# VGA.net
KiCad netlist of a schematic drawn in Altium Designer
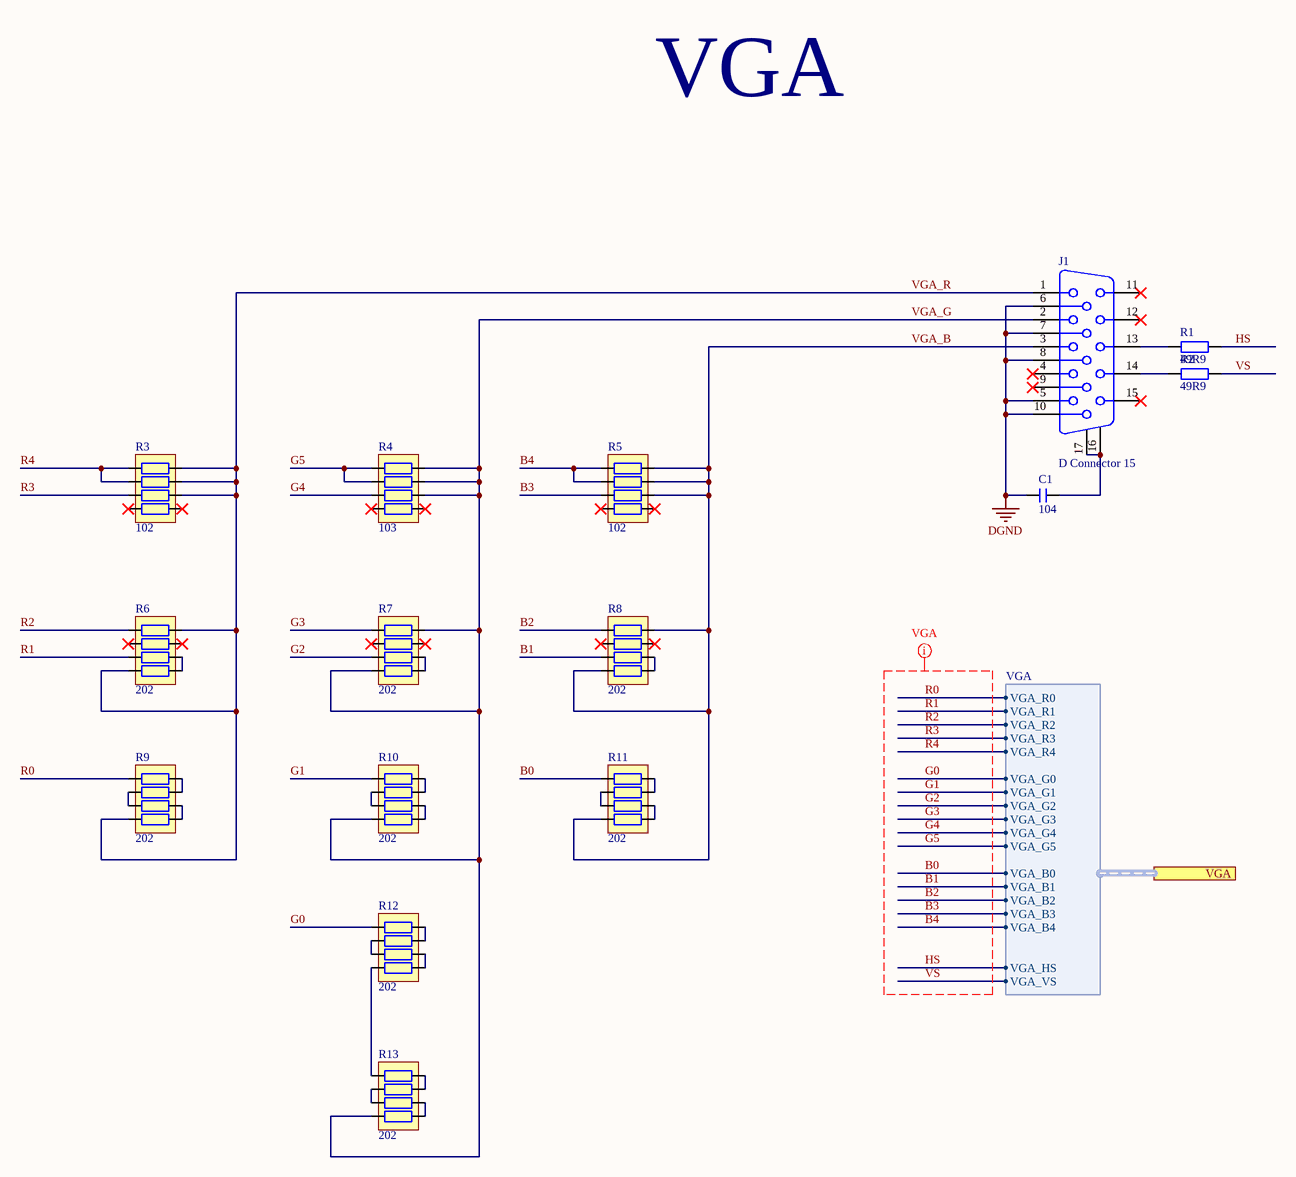
[diagram p0: VGA.SchDoc]

(export (version "E")
  (design (tool "Eeschema 10.0.6"))
  (components
    (comp (ref "C1")
      (value "104")
      (footprint "C 0402_M")
      (description "无极性贴片电容")
      (fields (field (name "版权归属") "源创客"))
      (libsource (lib "3.1   - 电阻-电容-电感") (part "C"))
    )
    (comp (ref "J1")
      (value "D Connector 15")
      (footprint "VGA15b")
      (description "VGA通讯端口")
      (fields (field (name "版权归属") "源创客"))
      (libsource (lib "4.1   - 接口类") (part "D Connector 15"))
    )
    (comp (ref "R1")
      (value "49R9")
      (footprint "R 0402_M")
      (description "贴片电阻")
      (fields (field (name "版权归属") "源创客"))
      (libsource (lib "3.1   - 电阻-电容-电感") (part "R"))
    )
    (comp (ref "R2")
      (value "49R9")
      (footprint "R 0402_M")
      (description "贴片电阻")
      (fields (field (name "版权归属") "源创客"))
      (libsource (lib "3.1   - 电阻-电容-电感") (part "R"))
    )
    (comp (ref "R3")
      (value "102")
      (footprint "RCA-8P4R-0402")
      (description "贴片网络排阻")
      (fields (field (name "版权归属") "源创客"))
      (libsource (lib "3.1   - 电阻-电容-电感") (part "R-8P4R"))
    )
    (comp (ref "R4")
      (value "103")
      (footprint "RCA-8P4R-0402")
      (description "贴片网络排阻")
      (fields (field (name "版权归属") "源创客"))
      (libsource (lib "3.1   - 电阻-电容-电感") (part "R-8P4R"))
    )
    (comp (ref "R5")
      (value "102")
      (footprint "RCA-8P4R-0402")
      (description "贴片网络排阻")
      (fields (field (name "版权归属") "源创客"))
      (libsource (lib "3.1   - 电阻-电容-电感") (part "R-8P4R"))
    )
    (comp (ref "R6")
      (value "202")
      (footprint "RCA-8P4R-0402")
      (description "贴片网络排阻")
      (fields (field (name "版权归属") "源创客"))
      (libsource (lib "3.1   - 电阻-电容-电感") (part "R-8P4R"))
    )
    (comp (ref "R7")
      (value "202")
      (footprint "RCA-8P4R-0402")
      (description "贴片网络排阻")
      (fields (field (name "版权归属") "源创客"))
      (libsource (lib "3.1   - 电阻-电容-电感") (part "R-8P4R"))
    )
    (comp (ref "R8")
      (value "202")
      (footprint "RCA-8P4R-0402")
      (description "贴片网络排阻")
      (fields (field (name "版权归属") "源创客"))
      (libsource (lib "3.1   - 电阻-电容-电感") (part "R-8P4R"))
    )
    (comp (ref "R9")
      (value "202")
      (footprint "RCA-8P4R-0402")
      (description "贴片网络排阻")
      (fields (field (name "版权归属") "源创客"))
      (libsource (lib "3.1   - 电阻-电容-电感") (part "R-8P4R"))
    )
    (comp (ref "R10")
      (value "202")
      (footprint "RCA-8P4R-0402")
      (description "贴片网络排阻")
      (fields (field (name "版权归属") "源创客"))
      (libsource (lib "3.1   - 电阻-电容-电感") (part "R-8P4R"))
    )
    (comp (ref "R11")
      (value "202")
      (footprint "RCA-8P4R-0402")
      (description "贴片网络排阻")
      (fields (field (name "版权归属") "源创客"))
      (libsource (lib "3.1   - 电阻-电容-电感") (part "R-8P4R"))
    )
    (comp (ref "R12")
      (value "202")
      (footprint "RCA-8P4R-0402")
      (description "贴片网络排阻")
      (fields (field (name "版权归属") "源创客"))
      (libsource (lib "3.1   - 电阻-电容-电感") (part "R-8P4R"))
    )
    (comp (ref "R13")
      (value "202")
      (footprint "RCA-8P4R-0402")
      (description "贴片网络排阻")
      (fields (field (name "版权归属") "源创客"))
      (libsource (lib "3.1   - 电阻-电容-电感") (part "R-8P4R"))
    )
  )
  (nets
    (net (code "2") (name "/B0") (class "Default")
      (node (ref "R11") (pin "1") (pinfunction "1_1") (pintype "passive"))
    )
    (net (code "3") (name "/B1") (class "Default")
      (node (ref "R8") (pin "3") (pinfunction "3_3") (pintype "passive"))
    )
    (net (code "4") (name "/B2") (class "Default")
      (node (ref "R8") (pin "1") (pinfunction "1_1") (pintype "passive"))
    )
    (net (code "5") (name "/B3") (class "Default")
      (node (ref "R5") (pin "3") (pinfunction "3_3") (pintype "passive"))
    )
    (net (code "6") (name "/B4") (class "Default")
      (node (ref "R5") (pin "1") (pinfunction "1_1") (pintype "passive"))
      (node (ref "R5") (pin "2") (pinfunction "2_2") (pintype "passive"))
    )
    (net (code "7") (name "/G0") (class "Default")
      (node (ref "R12") (pin "1") (pinfunction "1_1") (pintype "passive"))
    )
    (net (code "8") (name "/G1") (class "Default")
      (node (ref "R10") (pin "1") (pinfunction "1_1") (pintype "passive"))
    )
    (net (code "9") (name "/G2") (class "Default")
      (node (ref "R7") (pin "3") (pinfunction "3_3") (pintype "passive"))
    )
    (net (code "10") (name "/G3") (class "Default")
      (node (ref "R7") (pin "1") (pinfunction "1_1") (pintype "passive"))
    )
    (net (code "11") (name "/G4") (class "Default")
      (node (ref "R4") (pin "3") (pinfunction "3_3") (pintype "passive"))
    )
    (net (code "12") (name "/G5") (class "Default")
      (node (ref "R4") (pin "1") (pinfunction "1_1") (pintype "passive"))
      (node (ref "R4") (pin "2") (pinfunction "2_2") (pintype "passive"))
    )
    (net (code "13") (name "/HS") (class "Default")
      (node (ref "R1") (pin "1") (pinfunction "1_1") (pintype "passive"))
    )
    (net (code "14") (name "/R0") (class "Default")
      (node (ref "R9") (pin "1") (pinfunction "1_1") (pintype "passive"))
    )
    (net (code "15") (name "/R1") (class "Default")
      (node (ref "R6") (pin "3") (pinfunction "3_3") (pintype "passive"))
    )
    (net (code "16") (name "/R2") (class "Default")
      (node (ref "R6") (pin "1") (pinfunction "1_1") (pintype "passive"))
    )
    (net (code "17") (name "/R3") (class "Default")
      (node (ref "R3") (pin "3") (pinfunction "3_3") (pintype "passive"))
    )
    (net (code "18") (name "/R4") (class "Default")
      (node (ref "R3") (pin "1") (pinfunction "1_1") (pintype "passive"))
      (node (ref "R3") (pin "2") (pinfunction "2_2") (pintype "passive"))
    )
    (net (code "19") (name "/VGA_B") (class "Default")
      (node (ref "J1") (pin "3") (pinfunction "3_3") (pintype "passive"))
      (node (ref "R11") (pin "4") (pinfunction "4_4") (pintype "passive"))
      (node (ref "R5") (pin "6") (pinfunction "6_6") (pintype "passive"))
      (node (ref "R5") (pin "7") (pinfunction "7_7") (pintype "passive"))
      (node (ref "R5") (pin "8") (pinfunction "8_8") (pintype "passive"))
      (node (ref "R8") (pin "4") (pinfunction "4_4") (pintype "passive"))
      (node (ref "R8") (pin "8") (pinfunction "8_8") (pintype "passive"))
    )
    (net (code "20") (name "/VGA_G") (class "Default")
      (node (ref "J1") (pin "2") (pinfunction "2_2") (pintype "passive"))
      (node (ref "R10") (pin "4") (pinfunction "4_4") (pintype "passive"))
      (node (ref "R13") (pin "4") (pinfunction "4_4") (pintype "passive"))
      (node (ref "R4") (pin "6") (pinfunction "6_6") (pintype "passive"))
      (node (ref "R4") (pin "7") (pinfunction "7_7") (pintype "passive"))
      (node (ref "R4") (pin "8") (pinfunction "8_8") (pintype "passive"))
      (node (ref "R7") (pin "4") (pinfunction "4_4") (pintype "passive"))
      (node (ref "R7") (pin "8") (pinfunction "8_8") (pintype "passive"))
    )
    (net (code "21") (name "/VGA_R") (class "Default")
      (node (ref "J1") (pin "1") (pinfunction "1_1") (pintype "passive"))
      (node (ref "R3") (pin "6") (pinfunction "6_6") (pintype "passive"))
      (node (ref "R3") (pin "7") (pinfunction "7_7") (pintype "passive"))
      (node (ref "R3") (pin "8") (pinfunction "8_8") (pintype "passive"))
      (node (ref "R6") (pin "4") (pinfunction "4_4") (pintype "passive"))
      (node (ref "R6") (pin "8") (pinfunction "8_8") (pintype "passive"))
      (node (ref "R9") (pin "4") (pinfunction "4_4") (pintype "passive"))
    )
    (net (code "22") (name "/VS") (class "Default")
      (node (ref "R2") (pin "1") (pinfunction "1_1") (pintype "passive"))
    )
    (net (code "24") (name "DGND") (class "Default")
      (node (ref "C1") (pin "1") (pinfunction "1_1") (pintype "passive"))
      (node (ref "J1") (pin "10") (pinfunction "10_10") (pintype "passive"))
      (node (ref "J1") (pin "5") (pinfunction "5_5") (pintype "passive"))
      (node (ref "J1") (pin "6") (pinfunction "6_6") (pintype "passive"))
      (node (ref "J1") (pin "7") (pinfunction "7_7") (pintype "passive"))
      (node (ref "J1") (pin "8") (pinfunction "8_8") (pintype "passive"))
    )
    (net (code "25") (name "Net-(J1-MH1)") (class "Default")
      (node (ref "C1") (pin "2") (pinfunction "2_2") (pintype "passive"))
      (node (ref "J1") (pin "16") (pinfunction "MH2_16") (pintype "passive"))
      (node (ref "J1") (pin "17") (pinfunction "MH1_17") (pintype "passive"))
    )
    (net (code "26") (name "Net-(J1-Pad13)") (class "Default")
      (node (ref "J1") (pin "13") (pinfunction "13_13") (pintype "passive"))
      (node (ref "R1") (pin "2") (pinfunction "2_2") (pintype "passive"))
    )
    (net (code "27") (name "Net-(J1-Pad14)") (class "Default")
      (node (ref "J1") (pin "14") (pinfunction "14_14") (pintype "passive"))
      (node (ref "R2") (pin "2") (pinfunction "2_2") (pintype "passive"))
    )
    (net (code "28") (name "Net-(R6-Pad5)") (class "Default")
      (node (ref "R6") (pin "5") (pinfunction "5_5") (pintype "passive"))
      (node (ref "R6") (pin "6") (pinfunction "6_6") (pintype "passive"))
    )
    (net (code "29") (name "Net-(R7-Pad5)") (class "Default")
      (node (ref "R7") (pin "5") (pinfunction "5_5") (pintype "passive"))
      (node (ref "R7") (pin "6") (pinfunction "6_6") (pintype "passive"))
    )
    (net (code "30") (name "Net-(R8-Pad5)") (class "Default")
      (node (ref "R8") (pin "5") (pinfunction "5_5") (pintype "passive"))
      (node (ref "R8") (pin "6") (pinfunction "6_6") (pintype "passive"))
    )
    (net (code "31") (name "Net-(R9-Pad2)") (class "Default")
      (node (ref "R9") (pin "2") (pinfunction "2_2") (pintype "passive"))
      (node (ref "R9") (pin "3") (pinfunction "3_3") (pintype "passive"))
    )
    (net (code "32") (name "Net-(R9-Pad5)") (class "Default")
      (node (ref "R9") (pin "5") (pinfunction "5_5") (pintype "passive"))
      (node (ref "R9") (pin "6") (pinfunction "6_6") (pintype "passive"))
    )
    (net (code "33") (name "Net-(R9-Pad7)") (class "Default")
      (node (ref "R9") (pin "7") (pinfunction "7_7") (pintype "passive"))
      (node (ref "R9") (pin "8") (pinfunction "8_8") (pintype "passive"))
    )
    (net (code "34") (name "Net-(R10-Pad2)") (class "Default")
      (node (ref "R10") (pin "2") (pinfunction "2_2") (pintype "passive"))
      (node (ref "R10") (pin "3") (pinfunction "3_3") (pintype "passive"))
    )
    (net (code "35") (name "Net-(R10-Pad5)") (class "Default")
      (node (ref "R10") (pin "5") (pinfunction "5_5") (pintype "passive"))
      (node (ref "R10") (pin "6") (pinfunction "6_6") (pintype "passive"))
    )
    (net (code "36") (name "Net-(R10-Pad7)") (class "Default")
      (node (ref "R10") (pin "7") (pinfunction "7_7") (pintype "passive"))
      (node (ref "R10") (pin "8") (pinfunction "8_8") (pintype "passive"))
    )
    (net (code "37") (name "Net-(R11-Pad2)") (class "Default")
      (node (ref "R11") (pin "2") (pinfunction "2_2") (pintype "passive"))
      (node (ref "R11") (pin "3") (pinfunction "3_3") (pintype "passive"))
    )
    (net (code "38") (name "Net-(R11-Pad5)") (class "Default")
      (node (ref "R11") (pin "5") (pinfunction "5_5") (pintype "passive"))
      (node (ref "R11") (pin "6") (pinfunction "6_6") (pintype "passive"))
    )
    (net (code "39") (name "Net-(R11-Pad7)") (class "Default")
      (node (ref "R11") (pin "7") (pinfunction "7_7") (pintype "passive"))
      (node (ref "R11") (pin "8") (pinfunction "8_8") (pintype "passive"))
    )
    (net (code "40") (name "Net-(R12-Pad2)") (class "Default")
      (node (ref "R12") (pin "2") (pinfunction "2_2") (pintype "passive"))
      (node (ref "R12") (pin "3") (pinfunction "3_3") (pintype "passive"))
    )
    (net (code "41") (name "Net-(R12-Pad4)") (class "Default")
      (node (ref "R12") (pin "4") (pinfunction "4_4") (pintype "passive"))
      (node (ref "R13") (pin "1") (pinfunction "1_1") (pintype "passive"))
    )
    (net (code "42") (name "Net-(R12-Pad5)") (class "Default")
      (node (ref "R12") (pin "5") (pinfunction "5_5") (pintype "passive"))
      (node (ref "R12") (pin "6") (pinfunction "6_6") (pintype "passive"))
    )
    (net (code "43") (name "Net-(R12-Pad7)") (class "Default")
      (node (ref "R12") (pin "7") (pinfunction "7_7") (pintype "passive"))
      (node (ref "R12") (pin "8") (pinfunction "8_8") (pintype "passive"))
    )
    (net (code "44") (name "Net-(R13-Pad2)") (class "Default")
      (node (ref "R13") (pin "2") (pinfunction "2_2") (pintype "passive"))
      (node (ref "R13") (pin "3") (pinfunction "3_3") (pintype "passive"))
    )
    (net (code "45") (name "Net-(R13-Pad5)") (class "Default")
      (node (ref "R13") (pin "5") (pinfunction "5_5") (pintype "passive"))
      (node (ref "R13") (pin "6") (pinfunction "6_6") (pintype "passive"))
    )
    (net (code "46") (name "Net-(R13-Pad7)") (class "Default")
      (node (ref "R13") (pin "7") (pinfunction "7_7") (pintype "passive"))
      (node (ref "R13") (pin "8") (pinfunction "8_8") (pintype "passive"))
    )
    (net (code "47") (name "unconnected-(J1-Pad4)") (class "Default")
      (node (ref "J1") (pin "4") (pinfunction "4_4") (pintype "passive+no_connect"))
    )
    (net (code "48") (name "unconnected-(J1-Pad9)") (class "Default")
      (node (ref "J1") (pin "9") (pinfunction "9_9") (pintype "passive+no_connect"))
    )
    (net (code "49") (name "unconnected-(J1-Pad11)") (class "Default")
      (node (ref "J1") (pin "11") (pinfunction "11_11") (pintype "passive+no_connect"))
    )
    (net (code "50") (name "unconnected-(J1-Pad12)") (class "Default")
      (node (ref "J1") (pin "12") (pinfunction "12_12") (pintype "passive+no_connect"))
    )
    (net (code "51") (name "unconnected-(J1-Pad15)") (class "Default")
      (node (ref "J1") (pin "15") (pinfunction "15_15") (pintype "passive+no_connect"))
    )
    (net (code "52") (name "unconnected-(R3-Pad4)") (class "Default")
      (node (ref "R3") (pin "4") (pinfunction "4_4") (pintype "passive+no_connect"))
    )
    (net (code "53") (name "unconnected-(R3-Pad5)") (class "Default")
      (node (ref "R3") (pin "5") (pinfunction "5_5") (pintype "passive+no_connect"))
    )
    (net (code "54") (name "unconnected-(R4-Pad4)") (class "Default")
      (node (ref "R4") (pin "4") (pinfunction "4_4") (pintype "passive+no_connect"))
    )
    (net (code "55") (name "unconnected-(R4-Pad5)") (class "Default")
      (node (ref "R4") (pin "5") (pinfunction "5_5") (pintype "passive+no_connect"))
    )
    (net (code "56") (name "unconnected-(R5-Pad4)") (class "Default")
      (node (ref "R5") (pin "4") (pinfunction "4_4") (pintype "passive+no_connect"))
    )
    (net (code "57") (name "unconnected-(R5-Pad5)") (class "Default")
      (node (ref "R5") (pin "5") (pinfunction "5_5") (pintype "passive+no_connect"))
    )
    (net (code "58") (name "unconnected-(R6-Pad2)") (class "Default")
      (node (ref "R6") (pin "2") (pinfunction "2_2") (pintype "passive+no_connect"))
    )
    (net (code "59") (name "unconnected-(R6-Pad7)") (class "Default")
      (node (ref "R6") (pin "7") (pinfunction "7_7") (pintype "passive+no_connect"))
    )
    (net (code "60") (name "unconnected-(R7-Pad2)") (class "Default")
      (node (ref "R7") (pin "2") (pinfunction "2_2") (pintype "passive+no_connect"))
    )
    (net (code "61") (name "unconnected-(R7-Pad7)") (class "Default")
      (node (ref "R7") (pin "7") (pinfunction "7_7") (pintype "passive+no_connect"))
    )
    (net (code "62") (name "unconnected-(R8-Pad2)") (class "Default")
      (node (ref "R8") (pin "2") (pinfunction "2_2") (pintype "passive+no_connect"))
    )
    (net (code "63") (name "unconnected-(R8-Pad7)") (class "Default")
      (node (ref "R8") (pin "7") (pinfunction "7_7") (pintype "passive+no_connect"))
    )
  )
)
